# sterownik3.net
KiCad netlist of a schematic drawn in EAGLE
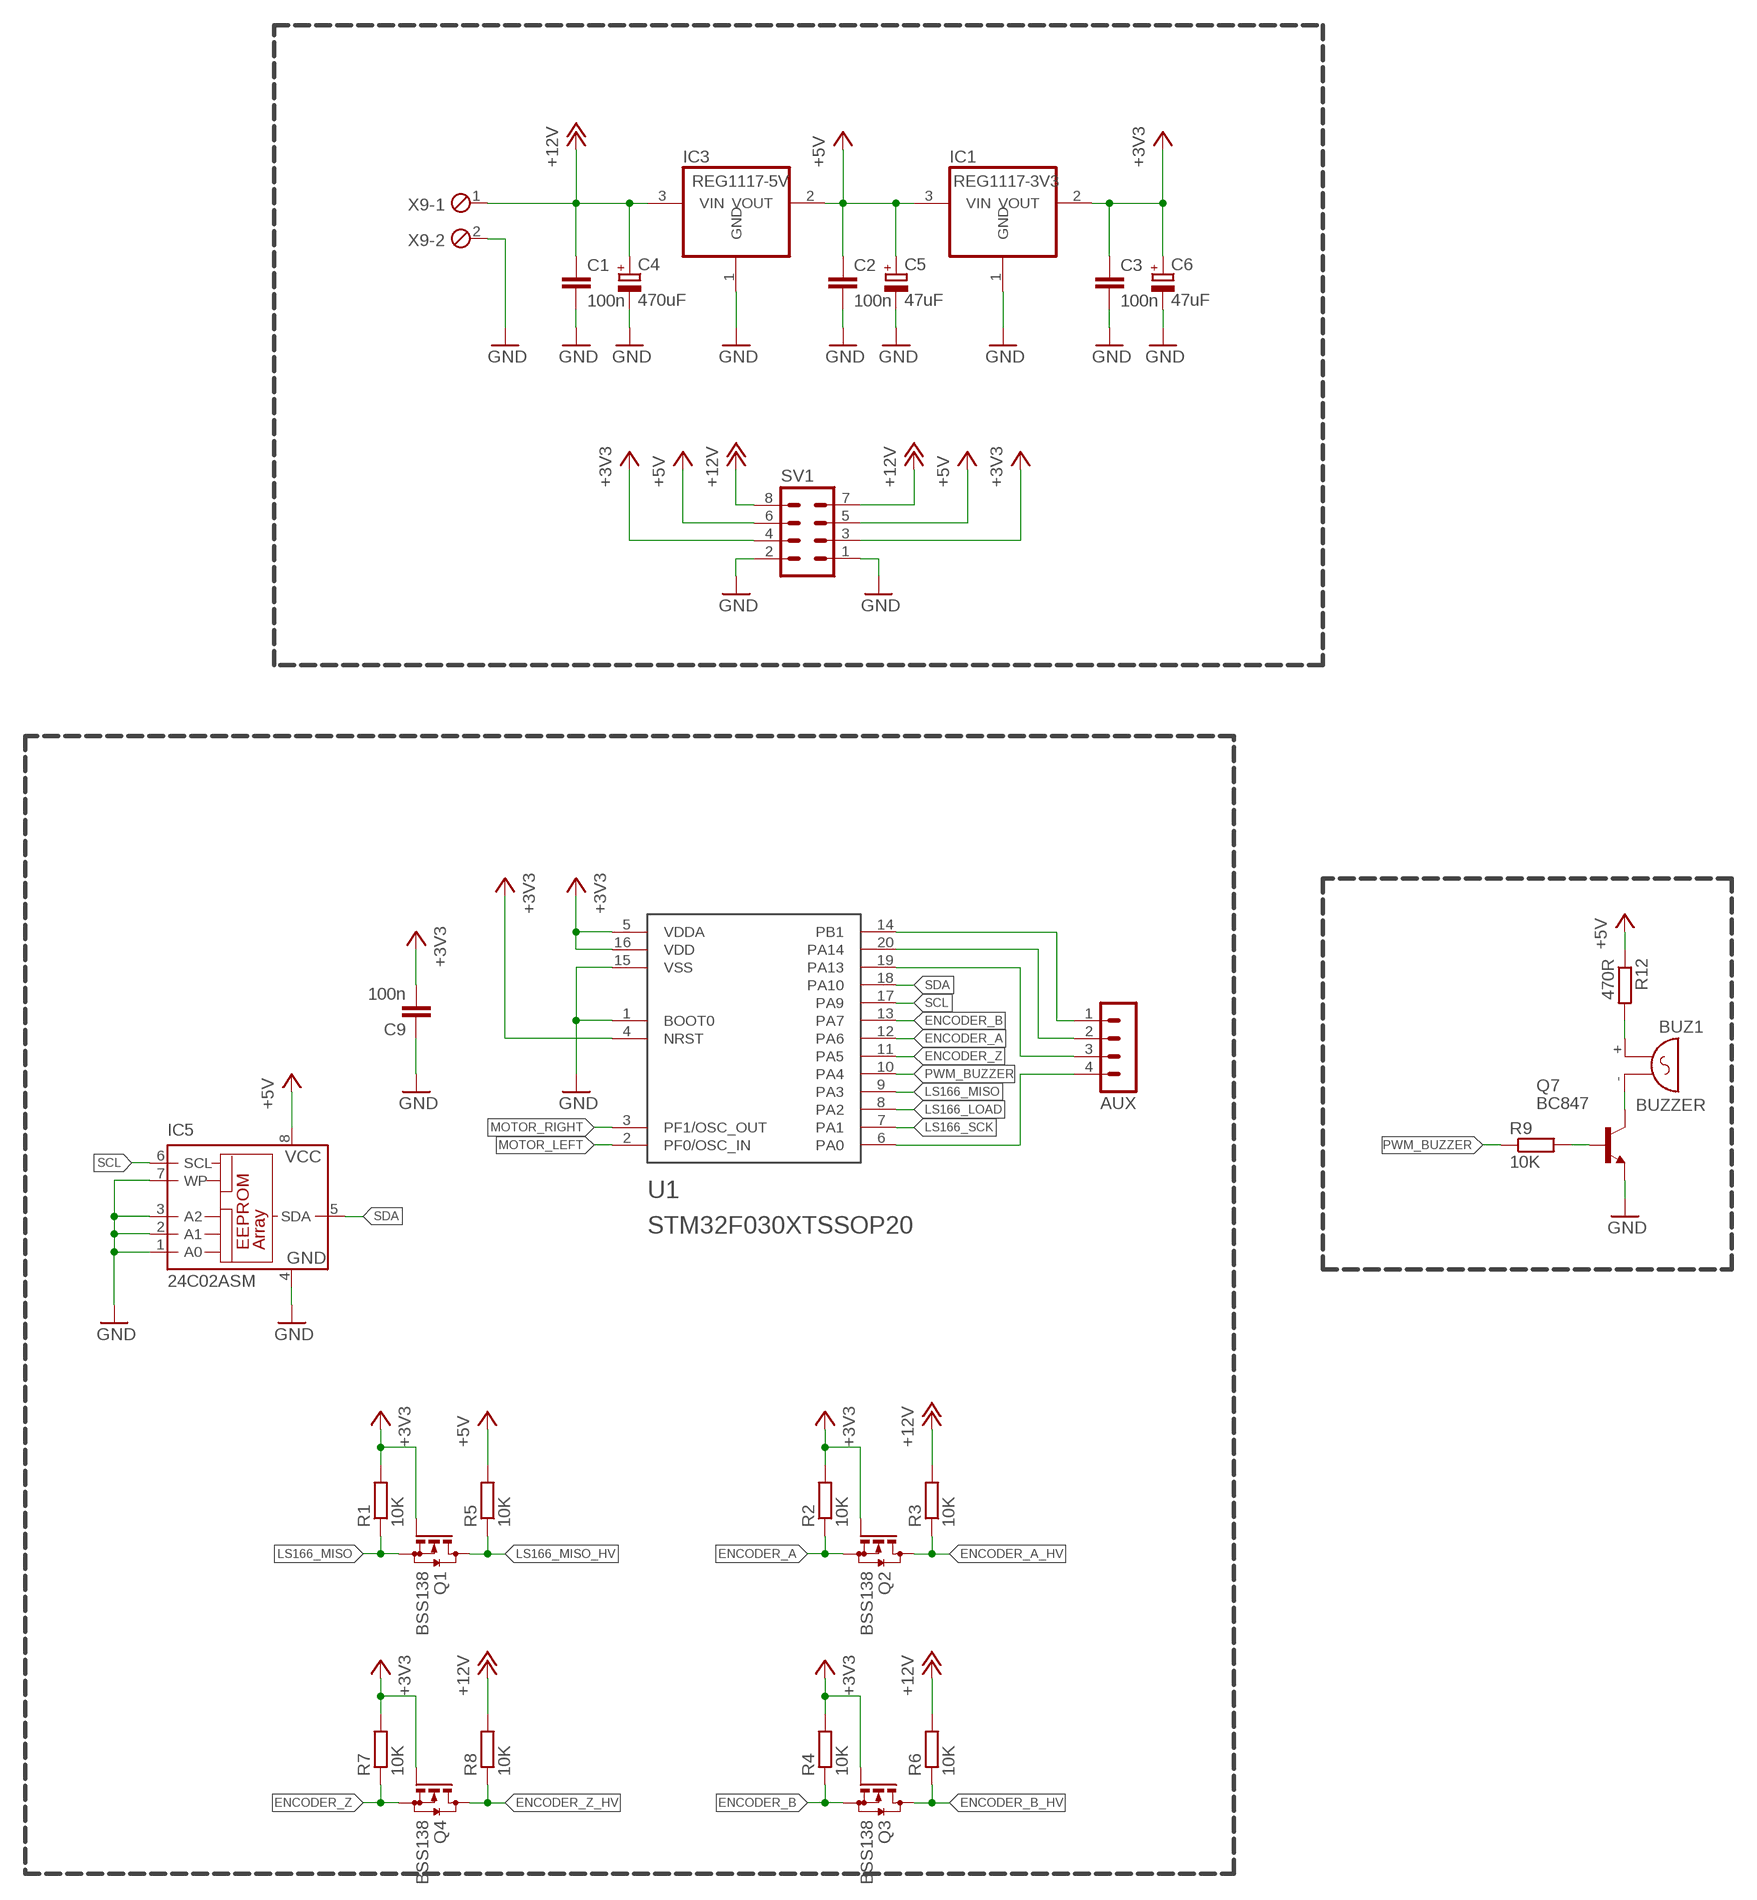
[diagram p0: schematic, sheet 1, part 1 of 2]
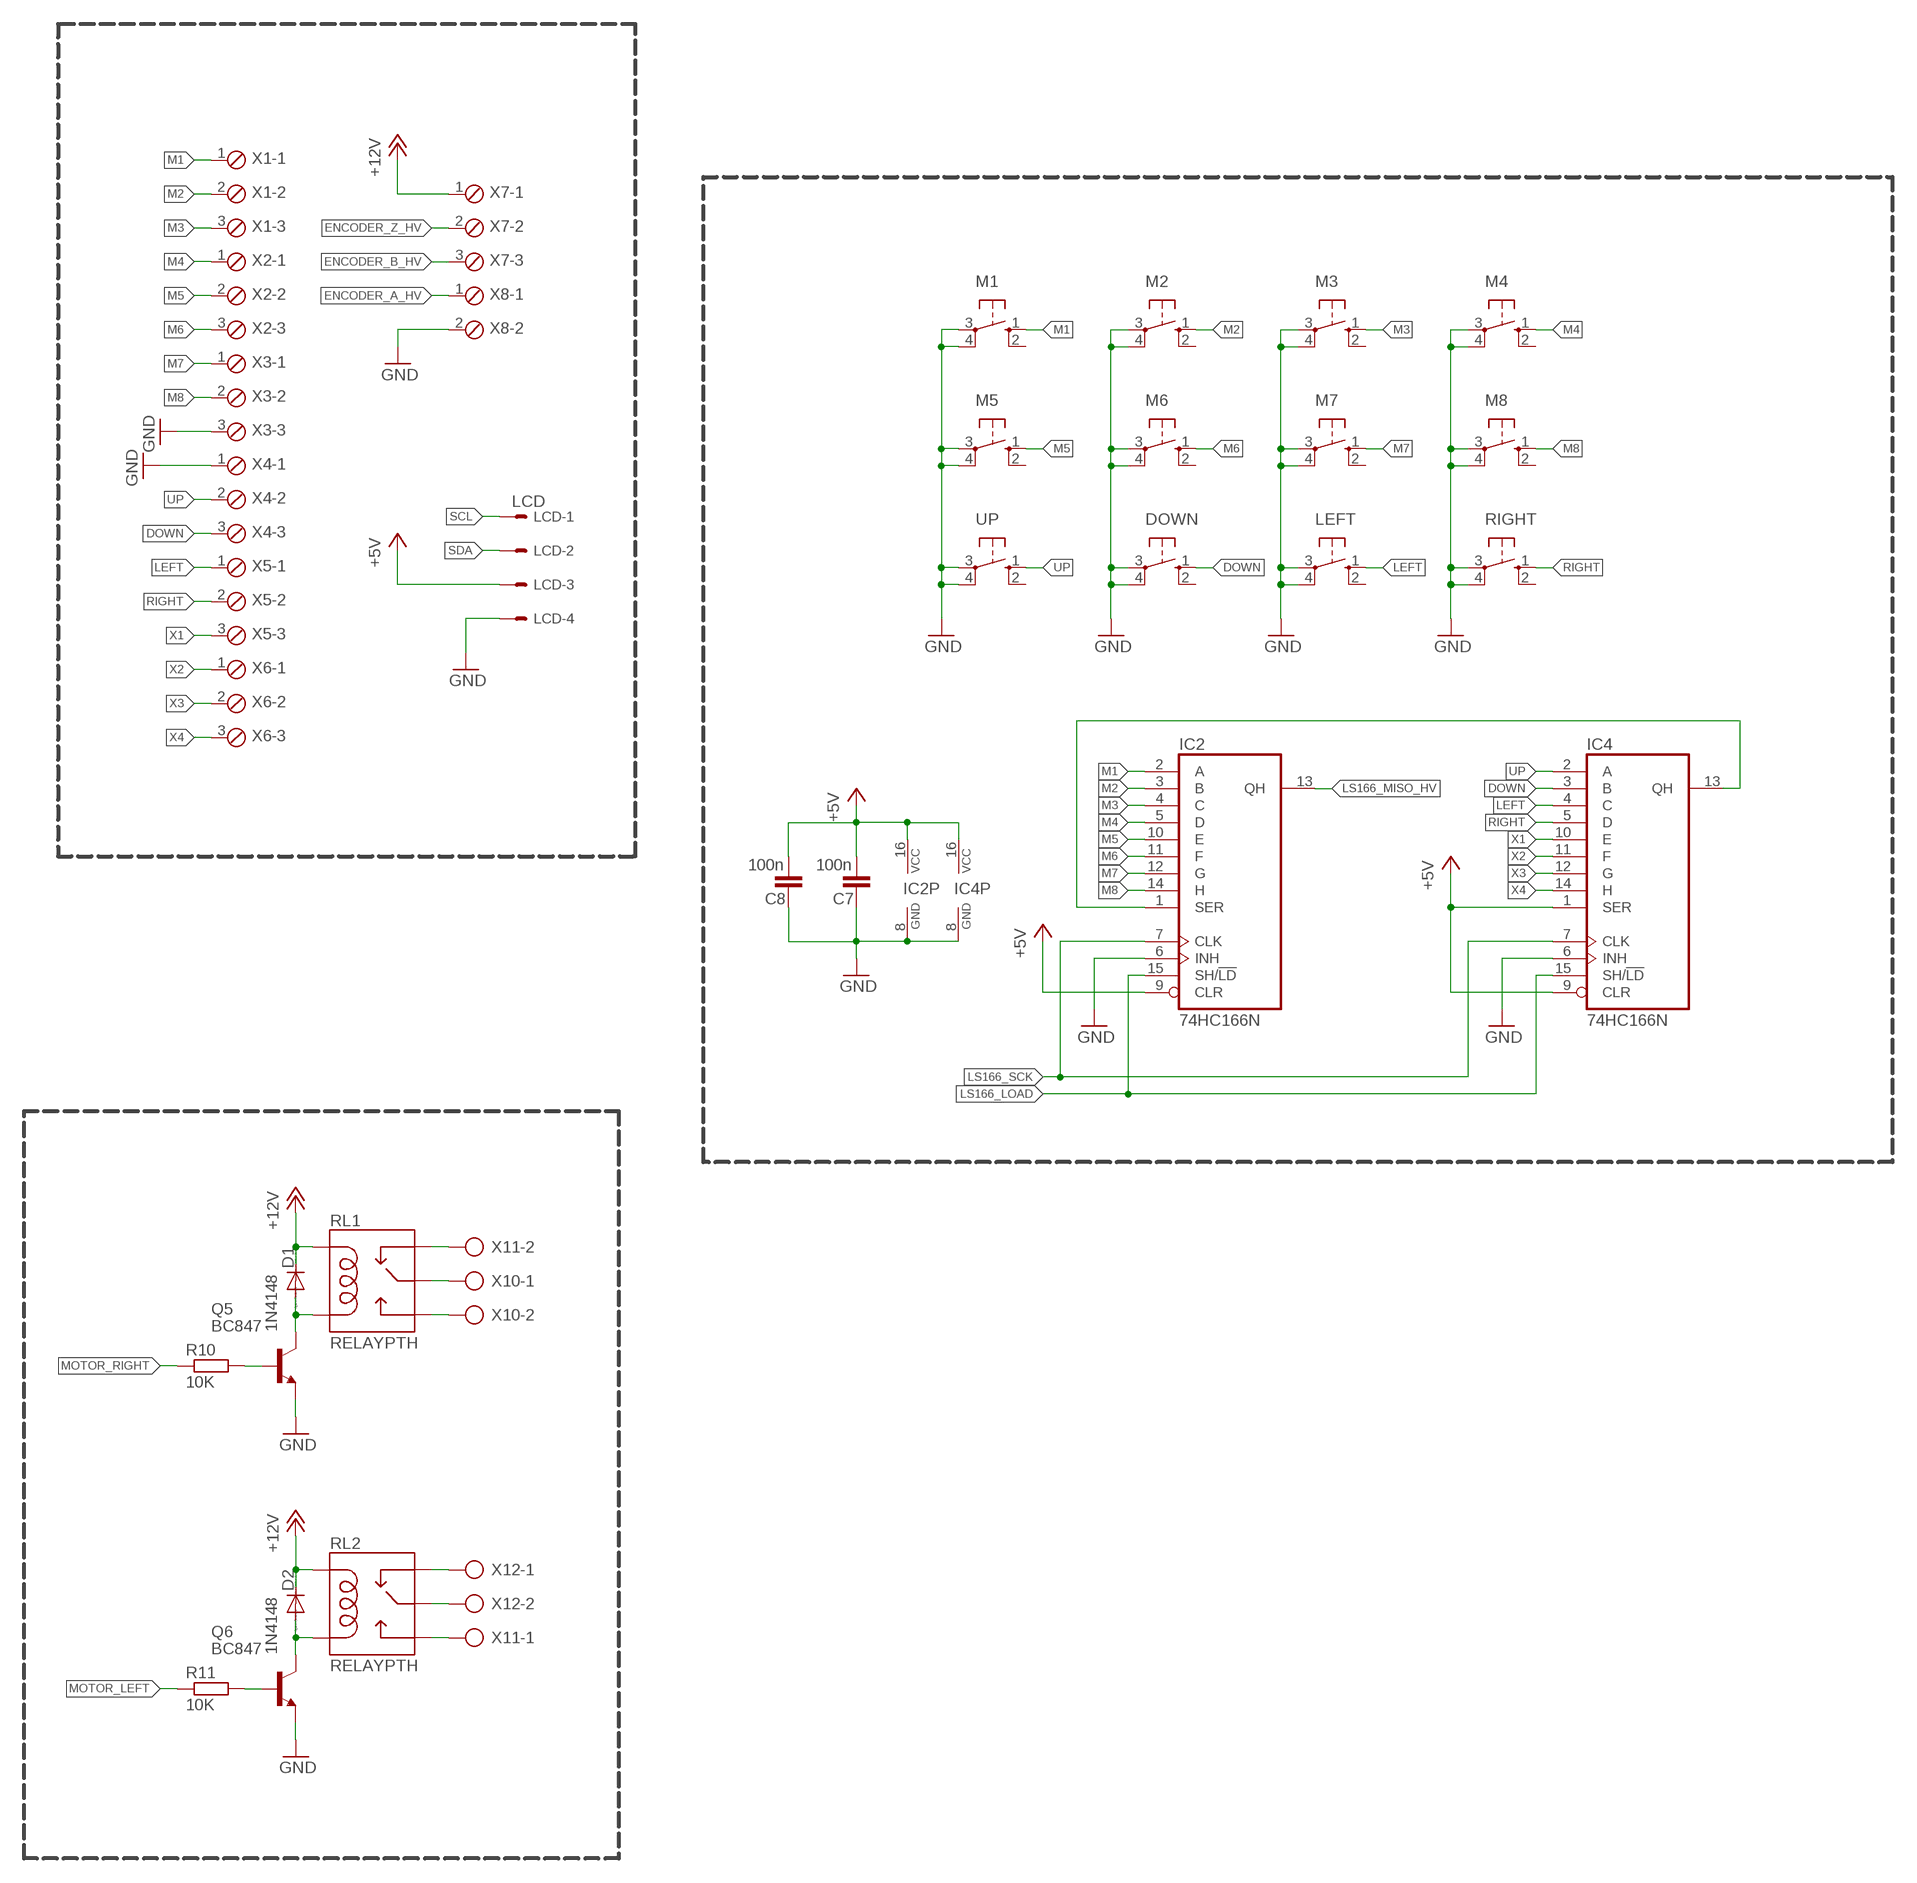
[diagram p1: schematic, sheet 1, part 2 of 2]

(export (version "E")
  (design (tool "Eeschema 10.0.6"))
  (components
    (comp (ref "AUX")
      (value "MA04-1")
      (footprint "eagle-import:MA04-1")
      (libsource (lib "eagle-import") (part "MA04-1"))
    )
    (comp (ref "BUZ1")
      (value "BUZZER")
      (footprint "eagle-import:F_QMX")
      (libsource (lib "eagle-import") (part "F/QMX"))
    )
    (comp (ref "C1")
      (value "100n")
      (footprint "eagle-import:C0805")
      (libsource (lib "eagle-import") (part "C-EUC0805"))
    )
    (comp (ref "C2")
      (value "100n")
      (footprint "eagle-import:C0805")
      (libsource (lib "eagle-import") (part "C-EUC0805"))
    )
    (comp (ref "C3")
      (value "100n")
      (footprint "eagle-import:C0805")
      (libsource (lib "eagle-import") (part "C-EUC0805"))
    )
    (comp (ref "C4")
      (value "470uF")
      (footprint "eagle-import:E5-8,5")
      (libsource (lib "eagle-import") (part "CPOL-EUE5-8.5"))
    )
    (comp (ref "C5")
      (value "47uF")
      (footprint "eagle-import:E5-6")
      (libsource (lib "eagle-import") (part "CPOL-EUE5-6"))
    )
    (comp (ref "C6")
      (value "47uF")
      (footprint "eagle-import:E5-6")
      (libsource (lib "eagle-import") (part "CPOL-EUE5-6"))
    )
    (comp (ref "C7")
      (value "100n")
      (footprint "eagle-import:C0805")
      (libsource (lib "eagle-import") (part "C-EUC0805"))
    )
    (comp (ref "C8")
      (value "100n")
      (footprint "eagle-import:C0805")
      (libsource (lib "eagle-import") (part "C-EUC0805"))
    )
    (comp (ref "C9")
      (value "100n")
      (footprint "eagle-import:C0805")
      (libsource (lib "eagle-import") (part "C-EUC0805"))
    )
    (comp (ref "D1")
      (value "1N4148")
      (footprint "eagle-import:DO35-7")
      (libsource (lib "eagle-import") (part "1N4148DO35-7"))
    )
    (comp (ref "D2")
      (value "1N4148")
      (footprint "eagle-import:DO35-7")
      (libsource (lib "eagle-import") (part "1N4148DO35-7"))
    )
    (comp (ref "DOWN")
      (value "10-XX")
      (footprint "eagle-import:B3F-10XX")
      (fields (field (name "MPN") "B3F-1000"))
      (libsource (lib "eagle-import") (part "10-XX"))
    )
    (comp (ref "IC1")
      (value "REG1117-3V3")
      (footprint "eagle-import:SOT223")
      (fields (field (name "MPN") "REG1117"))
      (libsource (lib "eagle-import") (part "REG1117"))
    )
    (comp (ref "IC2")
      (value "74HC166N")
      (footprint "eagle-import:DIL16")
      (libsource (lib "eagle-import") (part "74166NHC"))
    )
    (comp (ref "IC3")
      (value "REG1117-5V")
      (footprint "eagle-import:SOT223")
      (fields (field (name "MPN") "REG1117"))
      (libsource (lib "eagle-import") (part "REG1117"))
    )
    (comp (ref "IC4")
      (value "74HC166N")
      (footprint "eagle-import:DIL16")
      (libsource (lib "eagle-import") (part "74166NHC"))
    )
    (comp (ref "IC5")
      (value "24C02ASM")
      (footprint "eagle-import:SO-08M")
      (fields (field (name "MF") "MICROCHIP") (field (name "MPN") "24C02C/SN"))
      (libsource (lib "eagle-import") (part "24SMC02A"))
    )
    (comp (ref "LCD")
      (value "LCD")
      (footprint "eagle-import:6410-04")
      (libsource (lib "eagle-import") (part "22-?-0427-2041"))
    )
    (comp (ref "LEFT")
      (value "10-XX")
      (footprint "eagle-import:B3F-10XX")
      (fields (field (name "MPN") "B3F-1000"))
      (libsource (lib "eagle-import") (part "10-XX"))
    )
    (comp (ref "M1")
      (value "10-XX")
      (footprint "eagle-import:B3F-10XX")
      (fields (field (name "MPN") "B3F-1000"))
      (libsource (lib "eagle-import") (part "10-XX"))
    )
    (comp (ref "M2")
      (value "10-XX")
      (footprint "eagle-import:B3F-10XX")
      (fields (field (name "MPN") "B3F-1000"))
      (libsource (lib "eagle-import") (part "10-XX"))
    )
    (comp (ref "M3")
      (value "10-XX")
      (footprint "eagle-import:B3F-10XX")
      (fields (field (name "MPN") "B3F-1000"))
      (libsource (lib "eagle-import") (part "10-XX"))
    )
    (comp (ref "M4")
      (value "10-XX")
      (footprint "eagle-import:B3F-10XX")
      (fields (field (name "MPN") "B3F-1000"))
      (libsource (lib "eagle-import") (part "10-XX"))
    )
    (comp (ref "M5")
      (value "10-XX")
      (footprint "eagle-import:B3F-10XX")
      (fields (field (name "MPN") "B3F-1000"))
      (libsource (lib "eagle-import") (part "10-XX"))
    )
    (comp (ref "M6")
      (value "10-XX")
      (footprint "eagle-import:B3F-10XX")
      (fields (field (name "MPN") "B3F-1000"))
      (libsource (lib "eagle-import") (part "10-XX"))
    )
    (comp (ref "M7")
      (value "10-XX")
      (footprint "eagle-import:B3F-10XX")
      (fields (field (name "MPN") "B3F-1000"))
      (libsource (lib "eagle-import") (part "10-XX"))
    )
    (comp (ref "M8")
      (value "10-XX")
      (footprint "eagle-import:B3F-10XX")
      (fields (field (name "MPN") "B3F-1000"))
      (libsource (lib "eagle-import") (part "10-XX"))
    )
    (comp (ref "Q1")
      (value "BSS138")
      (footprint "eagle-import:SOT23")
      (libsource (lib "eagle-import") (part "BSS123"))
    )
    (comp (ref "Q2")
      (value "BSS138")
      (footprint "eagle-import:SOT23")
      (libsource (lib "eagle-import") (part "BSS123"))
    )
    (comp (ref "Q3")
      (value "BSS138")
      (footprint "eagle-import:SOT23")
      (libsource (lib "eagle-import") (part "BSS123"))
    )
    (comp (ref "Q4")
      (value "BSS138")
      (footprint "eagle-import:SOT23")
      (libsource (lib "eagle-import") (part "BSS123"))
    )
    (comp (ref "Q5")
      (value "BC847")
      (footprint "eagle-import:SOT23")
      (libsource (lib "eagle-import") (part "BC847"))
    )
    (comp (ref "Q6")
      (value "BC847")
      (footprint "eagle-import:SOT23")
      (libsource (lib "eagle-import") (part "BC847"))
    )
    (comp (ref "Q7")
      (value "BC847")
      (footprint "eagle-import:SOT23")
      (libsource (lib "eagle-import") (part "BC847"))
    )
    (comp (ref "R1")
      (value "10K")
      (footprint "eagle-import:R0805")
      (libsource (lib "eagle-import") (part "R-EU_R0805"))
    )
    (comp (ref "R2")
      (value "10K")
      (footprint "eagle-import:R0805")
      (libsource (lib "eagle-import") (part "R-EU_R0805"))
    )
    (comp (ref "R3")
      (value "10K")
      (footprint "eagle-import:R0805")
      (libsource (lib "eagle-import") (part "R-EU_R0805"))
    )
    (comp (ref "R4")
      (value "10K")
      (footprint "eagle-import:R0805")
      (libsource (lib "eagle-import") (part "R-EU_R0805"))
    )
    (comp (ref "R5")
      (value "10K")
      (footprint "eagle-import:R0805")
      (libsource (lib "eagle-import") (part "R-EU_R0805"))
    )
    (comp (ref "R6")
      (value "10K")
      (footprint "eagle-import:R0805")
      (libsource (lib "eagle-import") (part "R-EU_R0805"))
    )
    (comp (ref "R7")
      (value "10K")
      (footprint "eagle-import:R0805")
      (libsource (lib "eagle-import") (part "R-EU_R0805"))
    )
    (comp (ref "R8")
      (value "10K")
      (footprint "eagle-import:R0805")
      (libsource (lib "eagle-import") (part "R-EU_R0805"))
    )
    (comp (ref "R9")
      (value "10K")
      (footprint "eagle-import:R0805")
      (libsource (lib "eagle-import") (part "R-EU_R0805"))
    )
    (comp (ref "R10")
      (value "10K")
      (footprint "eagle-import:R0805")
      (libsource (lib "eagle-import") (part "R-EU_R0805"))
    )
    (comp (ref "R11")
      (value "10K")
      (footprint "eagle-import:R0805")
      (libsource (lib "eagle-import") (part "R-EU_R0805"))
    )
    (comp (ref "R12")
      (value "470R")
      (footprint "eagle-import:R0805")
      (libsource (lib "eagle-import") (part "R-EU_R0805"))
    )
    (comp (ref "RIGHT")
      (value "10-XX")
      (footprint "eagle-import:B3F-10XX")
      (fields (field (name "MPN") "B3F-1000"))
      (libsource (lib "eagle-import") (part "10-XX"))
    )
    (comp (ref "RL1")
      (value "RELAYPTH")
      (footprint "eagle-import:SRD-05VDC-SL-C")
      (libsource (lib "eagle-import") (part "RELAYPTH"))
    )
    (comp (ref "RL2")
      (value "RELAYPTH")
      (footprint "eagle-import:SRD-05VDC-SL-C")
      (libsource (lib "eagle-import") (part "RELAYPTH"))
    )
    (comp (ref "SV1")
      (value "MA04-2")
      (footprint "eagle-import:MA04-2")
      (libsource (lib "eagle-import") (part "MA04-2"))
    )
    (comp (ref "U1")
      (value "STM32F030XTSSOP20")
      (footprint "eagle-import:TSSOP-20")
      (libsource (lib "eagle-import") (part "STM32F030XTSSOP20"))
    )
    (comp (ref "UP")
      (value "10-XX")
      (footprint "eagle-import:B3F-10XX")
      (fields (field (name "MPN") "B3F-1000"))
      (libsource (lib "eagle-import") (part "10-XX"))
    )
    (comp (ref "X1")
      (value "MPT3")
      (footprint "eagle-import:3POL254")
      (libsource (lib "eagle-import") (part "MPT3"))
    )
    (comp (ref "X2")
      (value "MPT3")
      (footprint "eagle-import:3POL254")
      (libsource (lib "eagle-import") (part "MPT3"))
    )
    (comp (ref "X3")
      (value "MPT3")
      (footprint "eagle-import:3POL254")
      (libsource (lib "eagle-import") (part "MPT3"))
    )
    (comp (ref "X4")
      (value "MPT3")
      (footprint "eagle-import:3POL254")
      (libsource (lib "eagle-import") (part "MPT3"))
    )
    (comp (ref "X5")
      (value "MPT3")
      (footprint "eagle-import:3POL254")
      (libsource (lib "eagle-import") (part "MPT3"))
    )
    (comp (ref "X6")
      (value "MPT3")
      (footprint "eagle-import:3POL254")
      (libsource (lib "eagle-import") (part "MPT3"))
    )
    (comp (ref "X7")
      (value "MPT3")
      (footprint "eagle-import:3POL254")
      (libsource (lib "eagle-import") (part "MPT3"))
    )
    (comp (ref "X8")
      (value "MPT2")
      (footprint "eagle-import:2POL254")
      (libsource (lib "eagle-import") (part "MPT2"))
    )
    (comp (ref "X9")
      (value "MPT2")
      (footprint "eagle-import:2POL254")
      (libsource (lib "eagle-import") (part "MPT2"))
    )
    (comp (ref "X10")
      (value "AK500/2")
      (footprint "eagle-import:AK500_2")
      (libsource (lib "eagle-import") (part "AK500/2"))
    )
    (comp (ref "X11")
      (value "AK500/2")
      (footprint "eagle-import:AK500_2")
      (libsource (lib "eagle-import") (part "AK500/2"))
    )
    (comp (ref "X12")
      (value "AK500/2")
      (footprint "eagle-import:AK500_2")
      (libsource (lib "eagle-import") (part "AK500/2"))
    )
  )
  (nets
    (net (code "1") (name "+3V3") (class "Default")
      (node (ref "C3") (pin "1") (pinfunction "1_1") (pintype "passive"))
      (node (ref "C6") (pin "+") (pinfunction "+_+") (pintype "passive"))
      (node (ref "C9") (pin "2") (pinfunction "2_2") (pintype "passive"))
      (node (ref "IC1") (pin "2") (pinfunction "VOUT_2") (pintype "output"))
      (node (ref "Q1") (pin "1") (pinfunction "G_1") (pintype "passive"))
      (node (ref "Q2") (pin "1") (pinfunction "G_1") (pintype "passive"))
      (node (ref "Q3") (pin "1") (pinfunction "G_1") (pintype "passive"))
      (node (ref "Q4") (pin "1") (pinfunction "G_1") (pintype "passive"))
      (node (ref "R1") (pin "2") (pinfunction "2_2") (pintype "passive"))
      (node (ref "R2") (pin "2") (pinfunction "2_2") (pintype "passive"))
      (node (ref "R4") (pin "2") (pinfunction "2_2") (pintype "passive"))
      (node (ref "R7") (pin "2") (pinfunction "2_2") (pintype "passive"))
      (node (ref "SV1") (pin "3") (pinfunction "3_3") (pintype "passive"))
      (node (ref "SV1") (pin "4") (pinfunction "4_4") (pintype "passive"))
      (node (ref "U1") (pin "16") (pinfunction "VDD_16") (pintype "bidirectional"))
      (node (ref "U1") (pin "4") (pinfunction "NRST_4") (pintype "bidirectional"))
      (node (ref "U1") (pin "5") (pinfunction "VDDA_5") (pintype "bidirectional"))
    )
    (net (code "2") (name "+5V") (class "Default")
      (node (ref "C2") (pin "1") (pinfunction "1_1") (pintype "passive"))
      (node (ref "C5") (pin "+") (pinfunction "+_+") (pintype "passive"))
      (node (ref "C7") (pin "1") (pinfunction "1_1") (pintype "passive"))
      (node (ref "C8") (pin "1") (pinfunction "1_1") (pintype "passive"))
      (node (ref "IC1") (pin "3") (pinfunction "VIN_3") (pintype "input"))
      (node (ref "IC2") (pin "16") (pinfunction "VCC_16") (pintype "power_in"))
      (node (ref "IC2") (pin "9") (pinfunction "CLR_9") (pintype "input"))
      (node (ref "IC3") (pin "2") (pinfunction "VOUT_2") (pintype "output"))
      (node (ref "IC4") (pin "1") (pinfunction "SER_1") (pintype "input"))
      (node (ref "IC4") (pin "16") (pinfunction "VCC_16") (pintype "power_in"))
      (node (ref "IC4") (pin "9") (pinfunction "CLR_9") (pintype "input"))
      (node (ref "IC5") (pin "8") (pinfunction "VCC_8") (pintype "power_in"))
      (node (ref "LCD") (pin "3") (pinfunction "S_3") (pintype "passive"))
      (node (ref "R12") (pin "1") (pinfunction "1_1") (pintype "passive"))
      (node (ref "R5") (pin "2") (pinfunction "2_2") (pintype "passive"))
      (node (ref "SV1") (pin "5") (pinfunction "5_5") (pintype "passive"))
      (node (ref "SV1") (pin "6") (pinfunction "6_6") (pintype "passive"))
    )
    (net (code "3") (name "+12V") (class "Default")
      (node (ref "C1") (pin "1") (pinfunction "1_1") (pintype "passive"))
      (node (ref "C4") (pin "+") (pinfunction "+_+") (pintype "passive"))
      (node (ref "D1") (pin "C") (pinfunction "C_C") (pintype "passive"))
      (node (ref "D2") (pin "C") (pinfunction "C_C") (pintype "passive"))
      (node (ref "IC3") (pin "3") (pinfunction "VIN_3") (pintype "input"))
      (node (ref "R3") (pin "2") (pinfunction "2_2") (pintype "passive"))
      (node (ref "R6") (pin "2") (pinfunction "2_2") (pintype "passive"))
      (node (ref "R8") (pin "2") (pinfunction "2_2") (pintype "passive"))
      (node (ref "RL1") (pin "COIL1") (pinfunction "COIL1_COIL1") (pintype "bidirectional"))
      (node (ref "RL2") (pin "COIL1") (pinfunction "COIL1_COIL1") (pintype "bidirectional"))
      (node (ref "SV1") (pin "7") (pinfunction "7_7") (pintype "passive"))
      (node (ref "SV1") (pin "8") (pinfunction "8_8") (pintype "passive"))
      (node (ref "X7") (pin "1") (pinfunction "1_1") (pintype "passive"))
      (node (ref "X9") (pin "1") (pinfunction "1_1") (pintype "passive"))
    )
    (net (code "4") (name "DOWN") (class "Default")
      (node (ref "DOWN") (pin "1") (pinfunction "S_1") (pintype "passive"))
      (node (ref "IC4") (pin "3") (pinfunction "B_3") (pintype "input"))
      (node (ref "X4") (pin "3") (pinfunction "1_3") (pintype "passive"))
    )
    (net (code "5") (name "ENCODER_A") (class "Default")
      (node (ref "Q2") (pin "2") (pinfunction "S_2") (pintype "passive"))
      (node (ref "R2") (pin "1") (pinfunction "1_1") (pintype "passive"))
      (node (ref "U1") (pin "12") (pinfunction "PA6_12") (pintype "bidirectional"))
    )
    (net (code "6") (name "ENCODER_A_HV") (class "Default")
      (node (ref "Q2") (pin "3") (pinfunction "D_3") (pintype "passive"))
      (node (ref "R3") (pin "1") (pinfunction "1_1") (pintype "passive"))
      (node (ref "X8") (pin "1") (pinfunction "1_1") (pintype "passive"))
    )
    (net (code "7") (name "ENCODER_B") (class "Default")
      (node (ref "Q3") (pin "2") (pinfunction "S_2") (pintype "passive"))
      (node (ref "R4") (pin "1") (pinfunction "1_1") (pintype "passive"))
      (node (ref "U1") (pin "13") (pinfunction "PA7_13") (pintype "bidirectional"))
    )
    (net (code "8") (name "ENCODER_B_HV") (class "Default")
      (node (ref "Q3") (pin "3") (pinfunction "D_3") (pintype "passive"))
      (node (ref "R6") (pin "1") (pinfunction "1_1") (pintype "passive"))
      (node (ref "X7") (pin "3") (pinfunction "1_3") (pintype "passive"))
    )
    (net (code "9") (name "ENCODER_Z") (class "Default")
      (node (ref "Q4") (pin "2") (pinfunction "S_2") (pintype "passive"))
      (node (ref "R7") (pin "1") (pinfunction "1_1") (pintype "passive"))
      (node (ref "U1") (pin "11") (pinfunction "PA5_11") (pintype "bidirectional"))
    )
    (net (code "10") (name "ENCODER_Z_HV") (class "Default")
      (node (ref "Q4") (pin "3") (pinfunction "D_3") (pintype "passive"))
      (node (ref "R8") (pin "1") (pinfunction "1_1") (pintype "passive"))
      (node (ref "X7") (pin "2") (pinfunction "1_2") (pintype "passive"))
    )
    (net (code "11") (name "GND") (class "Default")
      (node (ref "C1") (pin "2") (pinfunction "2_2") (pintype "passive"))
      (node (ref "C2") (pin "2") (pinfunction "2_2") (pintype "passive"))
      (node (ref "C3") (pin "2") (pinfunction "2_2") (pintype "passive"))
      (node (ref "C4") (pin "-") (pinfunction "-_-") (pintype "passive"))
      (node (ref "C5") (pin "-") (pinfunction "-_-") (pintype "passive"))
      (node (ref "C6") (pin "-") (pinfunction "-_-") (pintype "passive"))
      (node (ref "C7") (pin "2") (pinfunction "2_2") (pintype "passive"))
      (node (ref "C8") (pin "2") (pinfunction "2_2") (pintype "passive"))
      (node (ref "C9") (pin "1") (pinfunction "1_1") (pintype "passive"))
      (node (ref "DOWN") (pin "3") (pinfunction "P_3") (pintype "passive"))
      (node (ref "DOWN") (pin "4") (pinfunction "P1_4") (pintype "passive"))
      (node (ref "IC1") (pin "1") (pinfunction "GND_1") (pintype "power_in"))
      (node (ref "IC2") (pin "6") (pinfunction "INH_6") (pintype "input"))
      (node (ref "IC2") (pin "8") (pinfunction "GND_8") (pintype "power_in"))
      (node (ref "IC3") (pin "1") (pinfunction "GND_1") (pintype "power_in"))
      (node (ref "IC4") (pin "6") (pinfunction "INH_6") (pintype "input"))
      (node (ref "IC4") (pin "8") (pinfunction "GND_8") (pintype "power_in"))
      (node (ref "IC5") (pin "1") (pinfunction "A0_1") (pintype "input"))
      (node (ref "IC5") (pin "2") (pinfunction "A1_2") (pintype "input"))
      (node (ref "IC5") (pin "3") (pinfunction "A2_3") (pintype "input"))
      (node (ref "IC5") (pin "4") (pinfunction "GND_4") (pintype "power_in"))
      (node (ref "IC5") (pin "7") (pinfunction "WP_7") (pintype "input"))
      (node (ref "LCD") (pin "4") (pinfunction "S_4") (pintype "passive"))
      (node (ref "LEFT") (pin "3") (pinfunction "P_3") (pintype "passive"))
      (node (ref "LEFT") (pin "4") (pinfunction "P1_4") (pintype "passive"))
      (node (ref "M1") (pin "3") (pinfunction "P_3") (pintype "passive"))
      (node (ref "M1") (pin "4") (pinfunction "P1_4") (pintype "passive"))
      (node (ref "M2") (pin "3") (pinfunction "P_3") (pintype "passive"))
      (node (ref "M2") (pin "4") (pinfunction "P1_4") (pintype "passive"))
      (node (ref "M3") (pin "3") (pinfunction "P_3") (pintype "passive"))
      (node (ref "M3") (pin "4") (pinfunction "P1_4") (pintype "passive"))
      (node (ref "M4") (pin "3") (pinfunction "P_3") (pintype "passive"))
      (node (ref "M4") (pin "4") (pinfunction "P1_4") (pintype "passive"))
      (node (ref "M5") (pin "3") (pinfunction "P_3") (pintype "passive"))
      (node (ref "M5") (pin "4") (pinfunction "P1_4") (pintype "passive"))
      (node (ref "M6") (pin "3") (pinfunction "P_3") (pintype "passive"))
      (node (ref "M6") (pin "4") (pinfunction "P1_4") (pintype "passive"))
      (node (ref "M7") (pin "3") (pinfunction "P_3") (pintype "passive"))
      (node (ref "M7") (pin "4") (pinfunction "P1_4") (pintype "passive"))
      (node (ref "M8") (pin "3") (pinfunction "P_3") (pintype "passive"))
      (node (ref "M8") (pin "4") (pinfunction "P1_4") (pintype "passive"))
      (node (ref "Q5") (pin "2") (pinfunction "E_2") (pintype "passive"))
      (node (ref "Q6") (pin "2") (pinfunction "E_2") (pintype "passive"))
      (node (ref "Q7") (pin "2") (pinfunction "E_2") (pintype "passive"))
      (node (ref "RIGHT") (pin "3") (pinfunction "P_3") (pintype "passive"))
      (node (ref "RIGHT") (pin "4") (pinfunction "P1_4") (pintype "passive"))
      (node (ref "SV1") (pin "1") (pinfunction "1_1") (pintype "passive"))
      (node (ref "SV1") (pin "2") (pinfunction "2_2") (pintype "passive"))
      (node (ref "U1") (pin "1") (pinfunction "BOOT0_1") (pintype "bidirectional"))
      (node (ref "U1") (pin "15") (pinfunction "VSS_15") (pintype "bidirectional"))
      (node (ref "UP") (pin "3") (pinfunction "P_3") (pintype "passive"))
      (node (ref "UP") (pin "4") (pinfunction "P1_4") (pintype "passive"))
      (node (ref "X3") (pin "3") (pinfunction "1_3") (pintype "passive"))
      (node (ref "X4") (pin "1") (pinfunction "1_1") (pintype "passive"))
      (node (ref "X8") (pin "2") (pinfunction "1_2") (pintype "passive"))
      (node (ref "X9") (pin "2") (pinfunction "1_2") (pintype "passive"))
    )
    (net (code "12") (name "LEFT") (class "Default")
      (node (ref "IC4") (pin "4") (pinfunction "C_4") (pintype "input"))
      (node (ref "LEFT") (pin "1") (pinfunction "S_1") (pintype "passive"))
      (node (ref "X5") (pin "1") (pinfunction "1_1") (pintype "passive"))
    )
    (net (code "13") (name "LS166_LOAD") (class "Default")
      (node (ref "IC2") (pin "15") (pinfunction "SH/~{LD}_15") (pintype "input"))
      (node (ref "IC4") (pin "15") (pinfunction "SH/~{LD}_15") (pintype "input"))
      (node (ref "U1") (pin "8") (pinfunction "PA2_8") (pintype "bidirectional"))
    )
    (net (code "14") (name "LS166_MISO") (class "Default")
      (node (ref "Q1") (pin "2") (pinfunction "S_2") (pintype "passive"))
      (node (ref "R1") (pin "1") (pinfunction "1_1") (pintype "passive"))
      (node (ref "U1") (pin "9") (pinfunction "PA3_9") (pintype "bidirectional"))
    )
    (net (code "15") (name "LS166_MISO_HV") (class "Default")
      (node (ref "IC2") (pin "13") (pinfunction "QH_13") (pintype "output"))
      (node (ref "Q1") (pin "3") (pinfunction "D_3") (pintype "passive"))
      (node (ref "R5") (pin "1") (pinfunction "1_1") (pintype "passive"))
    )
    (net (code "16") (name "LS166_SCK") (class "Default")
      (node (ref "IC2") (pin "7") (pinfunction "CLK_7") (pintype "input"))
      (node (ref "IC4") (pin "7") (pinfunction "CLK_7") (pintype "input"))
      (node (ref "U1") (pin "7") (pinfunction "PA1_7") (pintype "bidirectional"))
    )
    (net (code "17") (name "M1") (class "Default")
      (node (ref "IC2") (pin "2") (pinfunction "A_2") (pintype "input"))
      (node (ref "M1") (pin "1") (pinfunction "S_1") (pintype "passive"))
      (node (ref "X1") (pin "1") (pinfunction "1_1") (pintype "passive"))
    )
    (net (code "18") (name "M2") (class "Default")
      (node (ref "IC2") (pin "3") (pinfunction "B_3") (pintype "input"))
      (node (ref "M2") (pin "1") (pinfunction "S_1") (pintype "passive"))
      (node (ref "X1") (pin "2") (pinfunction "1_2") (pintype "passive"))
    )
    (net (code "19") (name "M3") (class "Default")
      (node (ref "IC2") (pin "4") (pinfunction "C_4") (pintype "input"))
      (node (ref "M3") (pin "1") (pinfunction "S_1") (pintype "passive"))
      (node (ref "X1") (pin "3") (pinfunction "1_3") (pintype "passive"))
    )
    (net (code "20") (name "M4") (class "Default")
      (node (ref "IC2") (pin "5") (pinfunction "D_5") (pintype "input"))
      (node (ref "M4") (pin "1") (pinfunction "S_1") (pintype "passive"))
      (node (ref "X2") (pin "1") (pinfunction "1_1") (pintype "passive"))
    )
    (net (code "21") (name "M5") (class "Default")
      (node (ref "IC2") (pin "10") (pinfunction "E_10") (pintype "input"))
      (node (ref "M5") (pin "1") (pinfunction "S_1") (pintype "passive"))
      (node (ref "X2") (pin "2") (pinfunction "1_2") (pintype "passive"))
    )
    (net (code "22") (name "M6") (class "Default")
      (node (ref "IC2") (pin "11") (pinfunction "F_11") (pintype "input"))
      (node (ref "M6") (pin "1") (pinfunction "S_1") (pintype "passive"))
      (node (ref "X2") (pin "3") (pinfunction "1_3") (pintype "passive"))
    )
    (net (code "23") (name "M7") (class "Default")
      (node (ref "IC2") (pin "12") (pinfunction "G_12") (pintype "input"))
      (node (ref "M7") (pin "1") (pinfunction "S_1") (pintype "passive"))
      (node (ref "X3") (pin "1") (pinfunction "1_1") (pintype "passive"))
    )
    (net (code "24") (name "M8") (class "Default")
      (node (ref "IC2") (pin "14") (pinfunction "H_14") (pintype "input"))
      (node (ref "M8") (pin "1") (pinfunction "S_1") (pintype "passive"))
      (node (ref "X3") (pin "2") (pinfunction "1_2") (pintype "passive"))
    )
    (net (code "25") (name "MOTOR_LEFT") (class "Default")
      (node (ref "R11") (pin "1") (pinfunction "1_1") (pintype "passive"))
      (node (ref "U1") (pin "2") (pinfunction "PF0/OSC_IN_2") (pintype "bidirectional"))
    )
    (net (code "26") (name "MOTOR_RIGHT") (class "Default")
      (node (ref "R10") (pin "1") (pinfunction "1_1") (pintype "passive"))
      (node (ref "U1") (pin "3") (pinfunction "PF1/OSC_OUT_3") (pintype "bidirectional"))
    )
    (net (code "27") (name "Net-(BUZ1-1)") (class "Default")
      (node (ref "BUZ1") (pin "-") (pinfunction "1_-") (pintype "passive"))
      (node (ref "Q7") (pin "3") (pinfunction "C_3") (pintype "passive"))
    )
    (net (code "28") (name "Net-(BUZ1-2)") (class "Default")
      (node (ref "BUZ1") (pin "+") (pinfunction "2_+") (pintype "passive"))
      (node (ref "R12") (pin "2") (pinfunction "2_2") (pintype "passive"))
    )
    (net (code "29") (name "Net-(IC2A-SER)") (class "Default")
      (node (ref "IC2") (pin "1") (pinfunction "SER_1") (pintype "input"))
      (node (ref "IC4") (pin "13") (pinfunction "QH_13") (pintype "output"))
    )
    (net (code "30") (name "Net-(Q5-B)") (class "Default")
      (node (ref "Q5") (pin "1") (pinfunction "B_1") (pintype "passive"))
      (node (ref "R10") (pin "2") (pinfunction "2_2") (pintype "passive"))
    )
    (net (code "31") (name "Net-(Q5-C)") (class "Default")
      (node (ref "D1") (pin "A") (pinfunction "A_A") (pintype "passive"))
      (node (ref "Q5") (pin "3") (pinfunction "C_3") (pintype "passive"))
      (node (ref "RL1") (pin "COIL0") (pinfunction "COIL0_COIL0") (pintype "bidirectional"))
    )
    (net (code "32") (name "Net-(Q6-B)") (class "Default")
      (node (ref "Q6") (pin "1") (pinfunction "B_1") (pintype "passive"))
      (node (ref "R11") (pin "2") (pinfunction "2_2") (pintype "passive"))
    )
    (net (code "33") (name "Net-(Q6-C)") (class "Default")
      (node (ref "D2") (pin "A") (pinfunction "A_A") (pintype "passive"))
      (node (ref "Q6") (pin "3") (pinfunction "C_3") (pintype "passive"))
      (node (ref "RL2") (pin "COIL0") (pinfunction "COIL0_COIL0") (pintype "bidirectional"))
    )
    (net (code "34") (name "Net-(Q7-B)") (class "Default")
      (node (ref "Q7") (pin "1") (pinfunction "B_1") (pintype "passive"))
      (node (ref "R9") (pin "2") (pinfunction "2_2") (pintype "passive"))
    )
    (net (code "35") (name "Net-(RL1-SWCLOSE)") (class "Default")
      (node (ref "RL1") (pin "SWCLOSED") (pinfunction "SWCLOSE_SWCLOSED") (pintype "bidirectional"))
      (node (ref "X11") (pin "2") (pinfunction "KL_2") (pintype "passive"))
    )
    (net (code "36") (name "Net-(RL2-SWCLOSE)") (class "Default")
      (node (ref "RL2") (pin "SWCLOSED") (pinfunction "SWCLOSE_SWCLOSED") (pintype "bidirectional"))
      (node (ref "X12") (pin "1") (pinfunction "KL_1") (pintype "passive"))
    )
    (net (code "37") (name "Net-(U1-PA0)") (class "Default")
      (node (ref "AUX") (pin "4") (pinfunction "4_4") (pintype "passive"))
      (node (ref "U1") (pin "6") (pinfunction "PA0_6") (pintype "bidirectional"))
    )
    (net (code "38") (name "Net-(U1-PA13)") (class "Default")
      (node (ref "AUX") (pin "3") (pinfunction "3_3") (pintype "passive"))
      (node (ref "U1") (pin "19") (pinfunction "PA13_19") (pintype "bidirectional"))
    )
    (net (code "39") (name "Net-(U1-PA14)") (class "Default")
      (node (ref "AUX") (pin "2") (pinfunction "2_2") (pintype "passive"))
      (node (ref "U1") (pin "20") (pinfunction "PA14_20") (pintype "bidirectional"))
    )
    (net (code "40") (name "Net-(U1-PB1)") (class "Default")
      (node (ref "AUX") (pin "1") (pinfunction "1_1") (pintype "passive"))
      (node (ref "U1") (pin "14") (pinfunction "PB1_14") (pintype "bidirectional"))
    )
    (net (code "41") (name "Net-(X10A-KL)") (class "Default")
      (node (ref "RL1") (pin "SWCOMMON") (pinfunction "SWCOMMON_SWCOMMON") (pintype "bidirectional"))
      (node (ref "X10") (pin "1") (pinfunction "KL_1") (pintype "passive"))
    )
    (net (code "42") (name "Net-(X10B-KL)") (class "Default")
      (node (ref "RL1") (pin "SWOPEN") (pinfunction "SWOPEN_SWOPEN") (pintype "bidirectional"))
      (node (ref "X10") (pin "2") (pinfunction "KL_2") (pintype "passive"))
    )
    (net (code "43") (name "Net-(X11A-KL)") (class "Default")
      (node (ref "RL2") (pin "SWOPEN") (pinfunction "SWOPEN_SWOPEN") (pintype "bidirectional"))
      (node (ref "X11") (pin "1") (pinfunction "KL_1") (pintype "passive"))
    )
    (net (code "44") (name "Net-(X12B-KL)") (class "Default")
      (node (ref "RL2") (pin "SWCOMMON") (pinfunction "SWCOMMON_SWCOMMON") (pintype "bidirectional"))
      (node (ref "X12") (pin "2") (pinfunction "KL_2") (pintype "passive"))
    )
    (net (code "45") (name "PWM_BUZZER") (class "Default")
      (node (ref "R9") (pin "1") (pinfunction "1_1") (pintype "passive"))
      (node (ref "U1") (pin "10") (pinfunction "PA4_10") (pintype "bidirectional"))
    )
    (net (code "46") (name "RIGHT") (class "Default")
      (node (ref "IC4") (pin "5") (pinfunction "D_5") (pintype "input"))
      (node (ref "RIGHT") (pin "1") (pinfunction "S_1") (pintype "passive"))
      (node (ref "X5") (pin "2") (pinfunction "1_2") (pintype "passive"))
    )
    (net (code "47") (name "SCL") (class "Default")
      (node (ref "IC5") (pin "6") (pinfunction "SCL_6") (pintype "input"))
      (node (ref "LCD") (pin "1") (pinfunction "S_1") (pintype "passive"))
      (node (ref "U1") (pin "17") (pinfunction "PA9_17") (pintype "bidirectional"))
    )
    (net (code "48") (name "SDA") (class "Default")
      (node (ref "IC5") (pin "5") (pinfunction "SDA_5") (pintype "bidirectional"))
      (node (ref "LCD") (pin "2") (pinfunction "S_2") (pintype "passive"))
      (node (ref "U1") (pin "18") (pinfunction "PA10_18") (pintype "bidirectional"))
    )
    (net (code "49") (name "UP") (class "Default")
      (node (ref "IC4") (pin "2") (pinfunction "A_2") (pintype "input"))
      (node (ref "UP") (pin "1") (pinfunction "S_1") (pintype "passive"))
      (node (ref "X4") (pin "2") (pinfunction "1_2") (pintype "passive"))
    )
    (net (code "50") (name "X1") (class "Default")
      (node (ref "IC4") (pin "10") (pinfunction "E_10") (pintype "input"))
      (node (ref "X5") (pin "3") (pinfunction "1_3") (pintype "passive"))
    )
    (net (code "51") (name "X2") (class "Default")
      (node (ref "IC4") (pin "11") (pinfunction "F_11") (pintype "input"))
      (node (ref "X6") (pin "1") (pinfunction "1_1") (pintype "passive"))
    )
    (net (code "52") (name "X3") (class "Default")
      (node (ref "IC4") (pin "12") (pinfunction "G_12") (pintype "input"))
      (node (ref "X6") (pin "2") (pinfunction "1_2") (pintype "passive"))
    )
    (net (code "53") (name "X4") (class "Default")
      (node (ref "IC4") (pin "14") (pinfunction "H_14") (pintype "input"))
      (node (ref "X6") (pin "3") (pinfunction "1_3") (pintype "passive"))
    )
    (net (code "54") (name "unconnected-(DOWN-S1-Pad2)") (class "Default")
      (node (ref "DOWN") (pin "2") (pinfunction "S1_2") (pintype "passive"))
    )
    (net (code "55") (name "unconnected-(LEFT-S1-Pad2)") (class "Default")
      (node (ref "LEFT") (pin "2") (pinfunction "S1_2") (pintype "passive"))
    )
    (net (code "56") (name "unconnected-(M1-S1-Pad2)") (class "Default")
      (node (ref "M1") (pin "2") (pinfunction "S1_2") (pintype "passive"))
    )
    (net (code "57") (name "unconnected-(M2-S1-Pad2)") (class "Default")
      (node (ref "M2") (pin "2") (pinfunction "S1_2") (pintype "passive"))
    )
    (net (code "58") (name "unconnected-(M3-S1-Pad2)") (class "Default")
      (node (ref "M3") (pin "2") (pinfunction "S1_2") (pintype "passive"))
    )
    (net (code "59") (name "unconnected-(M4-S1-Pad2)") (class "Default")
      (node (ref "M4") (pin "2") (pinfunction "S1_2") (pintype "passive"))
    )
    (net (code "60") (name "unconnected-(M5-S1-Pad2)") (class "Default")
      (node (ref "M5") (pin "2") (pinfunction "S1_2") (pintype "passive"))
    )
    (net (code "61") (name "unconnected-(M6-S1-Pad2)") (class "Default")
      (node (ref "M6") (pin "2") (pinfunction "S1_2") (pintype "passive"))
    )
    (net (code "62") (name "unconnected-(M7-S1-Pad2)") (class "Default")
      (node (ref "M7") (pin "2") (pinfunction "S1_2") (pintype "passive"))
    )
    (net (code "63") (name "unconnected-(M8-S1-Pad2)") (class "Default")
      (node (ref "M8") (pin "2") (pinfunction "S1_2") (pintype "passive"))
    )
    (net (code "64") (name "unconnected-(RIGHT-S1-Pad2)") (class "Default")
      (node (ref "RIGHT") (pin "2") (pinfunction "S1_2") (pintype "passive"))
    )
    (net (code "65") (name "unconnected-(UP-S1-Pad2)") (class "Default")
      (node (ref "UP") (pin "2") (pinfunction "S1_2") (pintype "passive"))
    )
  )
)
